# BLUENRG-M2SP.net
KiCad netlist of a schematic drawn in Altium Designer
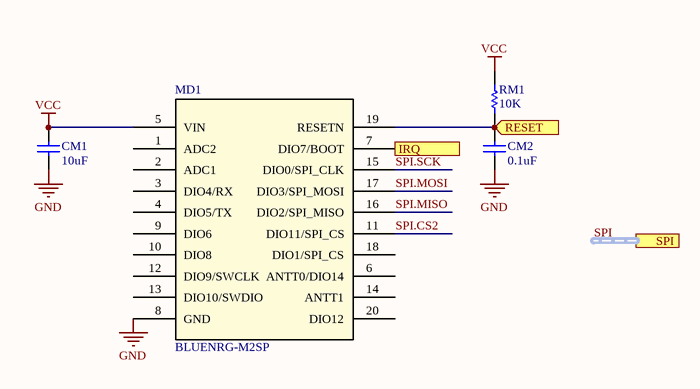
[diagram p0: BLUENRG-M2SP.SchDoc]

(export (version "E")
  (design (tool "Eeschema 10.0.6"))
  (components
    (comp (ref "CM1")
      (value "10uF")
      (footprint "C0603[1608X92]")
      (description "10uF 6.3V 10% 0603 (1608 Metric)")
      (fields (field (name "PARTNUMBER") "GRM188R60J106KE47D") (field (name "MANUFACTURER") "Murata"))
      (libsource (lib "Capacitors") (part "CAP_10uF_6.3V_0603_10%"))
    )
    (comp (ref "CM2")
      (value "0.1uF")
      (footprint "C0603[1608X92]")
      (description "0.1uF 16V 10% 0603 (1608 Metric)")
      (fields (field (name "PARTNUMBER") "GCM188R71C104KA37D") (field (name "MANUFACTURER") "Murata"))
      (libsource (lib "Capacitors") (part "CAP_0.1uF_16V_0603_10%"))
    )
    (comp (ref "MD1")
      (value "BLUENRG-M2SP")
      (footprint "BLUENRG-M2SP")
      (fields (field (name "MANUFACTURER") "STMicroelectronics"))
      (libsource (lib "Modules") (part "BLUENRG-M2SP"))
    )
    (comp (ref "RM1")
      (value "10K")
      (footprint "R0603[1608]")
      (description "10K 0.25W 1% 0603 (1005 Metric)")
      (fields (field (name "MANUFACTURER") "Vishay / Dale") (field (name "PARTNUMBER") "CRCW060310K0FKEAHP"))
      (libsource (lib "Resistors") (part "RES_10K_0603_1%"))
    )
  )
  (nets
    (net (code "2") (name "/IRQ") (class "Default")
      (node (ref "MD1") (pin "7") (pinfunction "DIO7/BOOT_7") (pintype "passive"))
    )
    (net (code "3") (name "/RESET") (class "Default")
      (node (ref "CM2") (pin "1") (pinfunction "1_1") (pintype "passive"))
      (node (ref "MD1") (pin "19") (pinfunction "RESETN_19") (pintype "passive"))
      (node (ref "RM1") (pin "1") (pinfunction "1_1") (pintype "passive"))
    )
    (net (code "4") (name "/SPI.CS2") (class "Default")
      (node (ref "MD1") (pin "11") (pinfunction "DIO11/SPI_CS_11") (pintype "passive"))
    )
    (net (code "5") (name "/SPI.MISO") (class "Default")
      (node (ref "MD1") (pin "16") (pinfunction "DIO2/SPI_MISO_16") (pintype "passive"))
    )
    (net (code "6") (name "/SPI.MOSI") (class "Default")
      (node (ref "MD1") (pin "17") (pinfunction "DIO3/SPI_MOSI_17") (pintype "passive"))
    )
    (net (code "7") (name "/SPI.SCK") (class "Default")
      (node (ref "MD1") (pin "15") (pinfunction "DIO0/SPI_CLK_15") (pintype "passive"))
    )
    (net (code "9") (name "GND") (class "Default")
      (node (ref "CM1") (pin "2") (pinfunction "2_2") (pintype "passive"))
      (node (ref "CM2") (pin "2") (pinfunction "2_2") (pintype "passive"))
      (node (ref "MD1") (pin "8") (pinfunction "GND_8") (pintype "power_in"))
    )
    (net (code "10") (name "VCC") (class "Default")
      (node (ref "CM1") (pin "1") (pinfunction "1_1") (pintype "passive"))
      (node (ref "MD1") (pin "5") (pinfunction "VIN_5") (pintype "power_in"))
      (node (ref "RM1") (pin "2") (pinfunction "2_2") (pintype "passive"))
    )
    (net (code "11") (name "unconnected-(MD1-ADC1-Pad2)") (class "Default")
      (node (ref "MD1") (pin "2") (pinfunction "ADC1_2") (pintype "passive"))
    )
    (net (code "12") (name "unconnected-(MD1-ADC2-Pad1)") (class "Default")
      (node (ref "MD1") (pin "1") (pinfunction "ADC2_1") (pintype "passive"))
    )
    (net (code "13") (name "unconnected-(MD1-ANTT0{slash}DIO14-Pad6)") (class "Default")
      (node (ref "MD1") (pin "6") (pinfunction "ANTT0/DIO14_6") (pintype "passive"))
    )
    (net (code "14") (name "unconnected-(MD1-ANTT1-Pad14)") (class "Default")
      (node (ref "MD1") (pin "14") (pinfunction "ANTT1_14") (pintype "passive"))
    )
    (net (code "15") (name "unconnected-(MD1-DIO1{slash}SPI_CS-Pad18)") (class "Default")
      (node (ref "MD1") (pin "18") (pinfunction "DIO1/SPI_CS_18") (pintype "passive"))
    )
    (net (code "16") (name "unconnected-(MD1-DIO4{slash}RX-Pad3)") (class "Default")
      (node (ref "MD1") (pin "3") (pinfunction "DIO4/RX_3") (pintype "passive"))
    )
    (net (code "17") (name "unconnected-(MD1-DIO5{slash}TX-Pad4)") (class "Default")
      (node (ref "MD1") (pin "4") (pinfunction "DIO5/TX_4") (pintype "passive"))
    )
    (net (code "18") (name "unconnected-(MD1-DIO6-Pad9)") (class "Default")
      (node (ref "MD1") (pin "9") (pinfunction "DIO6_9") (pintype "power_in"))
    )
    (net (code "19") (name "unconnected-(MD1-DIO8-Pad10)") (class "Default")
      (node (ref "MD1") (pin "10") (pinfunction "DIO8_10") (pintype "passive"))
    )
    (net (code "20") (name "unconnected-(MD1-DIO9{slash}SWCLK-Pad12)") (class "Default")
      (node (ref "MD1") (pin "12") (pinfunction "DIO9/SWCLK_12") (pintype "passive"))
    )
    (net (code "21") (name "unconnected-(MD1-DIO10{slash}SWDIO-Pad13)") (class "Default")
      (node (ref "MD1") (pin "13") (pinfunction "DIO10/SWDIO_13") (pintype "passive"))
    )
    (net (code "22") (name "unconnected-(MD1-DIO12-Pad20)") (class "Default")
      (node (ref "MD1") (pin "20") (pinfunction "DIO12_20") (pintype "passive"))
    )
  )
)
